# Sheet1.net
KiCad netlist of a schematic drawn in Altium Designer
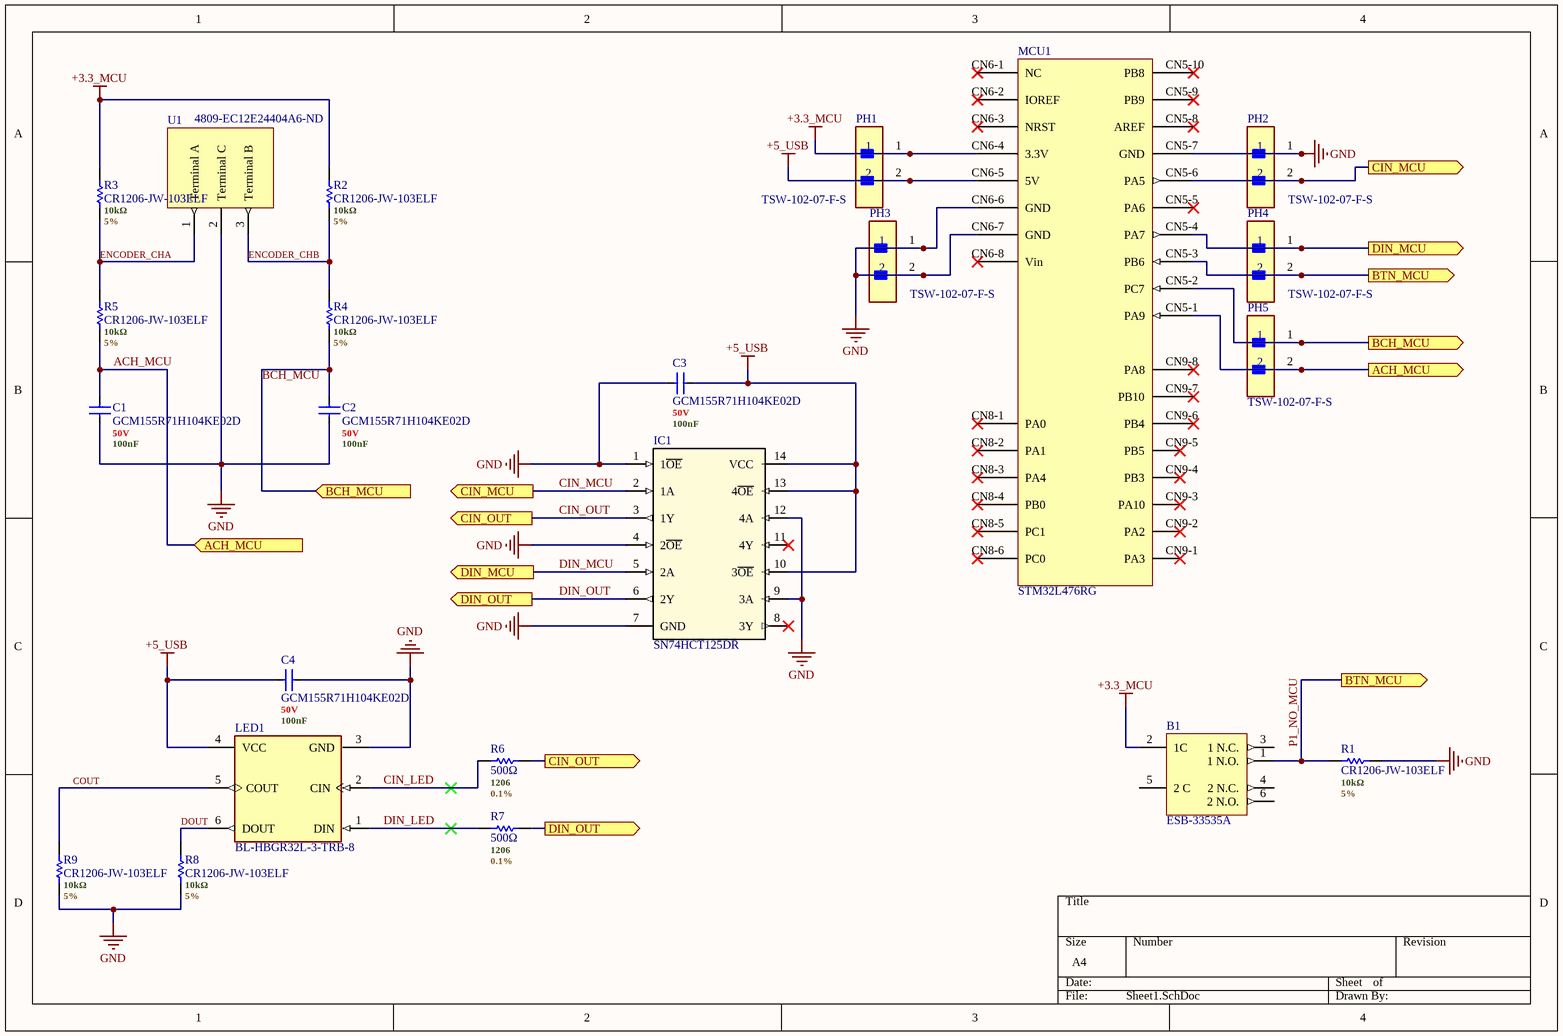
[diagram p0: Sheet1.SchDoc]

(export (version "E")
  (design (tool "Eeschema 10.0.6"))
  (components
    (comp (ref "B1")
      (value "ESB-33535A")
      (footprint "SOIC_Boton")
      (description "Pushbutton Switch, DPDT, Momentary, 0.2A, 14VDC, Solder Terminal, Surface Mount-straight")
      (fields (field (name "MANUFACTURER") "Panasonic"))
      (libsource (lib "Button") (part "ESB-33535A"))
    )
    (comp (ref "C1")
      (value "GCM155R71H104KE02D")
      (footprint "GCM155R71H104KE02D")
      (description "50V 100nF X7R ±10% 0402 Multilayer Ceramic Capacitors MLCC - SMD/SMT ROHS")
      (fields
        (field (name "MANUFACTURER") "Murata")
        (field (name "TOLERANCE") "10%")
        (field (name ".VOLTAGE RATING (DC)") "50V")
        (field (name ".VALUE") "100nF")
      )
      (libsource (lib "CAPACITOR_100nF") (part "GCM155R71H104KE02D"))
    )
    (comp (ref "C2")
      (value "GCM155R71H104KE02D")
      (footprint "GCM155R71H104KE02D")
      (description "50V 100nF X7R ±10% 0402 Multilayer Ceramic Capacitors MLCC - SMD/SMT ROHS")
      (fields
        (field (name "MANUFACTURER") "Murata")
        (field (name "TOLERANCE") "10%")
        (field (name ".VOLTAGE RATING (DC)") "50V")
        (field (name ".VALUE") "100nF")
      )
      (libsource (lib "CAPACITOR_100nF") (part "GCM155R71H104KE02D"))
    )
    (comp (ref "C3")
      (value "GCM155R71H104KE02D")
      (footprint "GCM155R71H104KE02D")
      (description "50V 100nF X7R ±10% 0402 Multilayer Ceramic Capacitors MLCC - SMD/SMT ROHS")
      (fields
        (field (name "MANUFACTURER") "Murata")
        (field (name "TOLERANCE") "10%")
        (field (name ".VOLTAGE RATING (DC)") "50V")
        (field (name ".VALUE") "100nF")
      )
      (libsource (lib "CAPACITOR_100nF") (part "GCM155R71H104KE02D"))
    )
    (comp (ref "C4")
      (value "GCM155R71H104KE02D")
      (footprint "GCM155R71H104KE02D")
      (description "50V 100nF X7R ±10% 0402 Multilayer Ceramic Capacitors MLCC - SMD/SMT ROHS")
      (fields
        (field (name "MANUFACTURER") "Murata")
        (field (name "TOLERANCE") "10%")
        (field (name ".VOLTAGE RATING (DC)") "50V")
        (field (name ".VALUE") "100nF")
      )
      (libsource (lib "CAPACITOR_100nF") (part "GCM155R71H104KE02D"))
    )
    (comp (ref "IC1")
      (value "SN74HCT125DR")
      (footprint "SOIC127P600X175_HS-15N - TI")
      (description "Buffer/Line Driver 4-CH Non-Inverting 3-ST CMOS 14-Pin SOIC T/R / IC BUS BUFF TRI-ST QD 14SOIC")
      (fields (field (name "MANUFACTURER") "Texas Instruments"))
      (libsource (lib "LVL_SHFT_SN74HCT125DR") (part "SN74HCT125DR"))
    )
    (comp (ref "LED1")
      (value "BL-HBGR32L-3-TRB-8")
      (footprint "SOIC_LEDRGB")
      (description "Address Led Discrete Serial Rgb")
      (fields (field (name "MANUFACTURER") "American Bright"))
      (libsource (lib "LED_RGB") (part "BL-HBGR32L-3-TRB-8"))
    )
    (comp (ref "MCU1")
      (value "STM32L476RG")
      (footprint "Nucleo_Card")
      (description "Development Board, STM32L476RG MCU, On-Board STLINK/V2-1, Arduino & ST Morpho Connectivity")
      (fields
        (field (name "MANUFACTURER") "STMicroelectronics")
        (field (name "MANUFACTURER PART NUMBER") "NUCLEO-L476RG")
      )
      (libsource (lib "MCU_Generico") (part "STM32L476RG"))
    )
    (comp (ref "PH1")
      (value "TSW-102-07-F-S")
      (footprint "TSW-102-07-F-S")
      (description "2 Positions Header, Unshrouded Connector 0.100\" (2.54mm) Through Hole Gold")
      (fields (field (name "MANUFACTURER") "Samtec"))
      (libsource (lib "PIN") (part "TSW-102-07-F-S"))
    )
    (comp (ref "PH2")
      (value "TSW-102-07-F-S")
      (footprint "TSW-102-07-F-S")
      (description "2 Positions Header, Unshrouded Connector 0.100\" (2.54mm) Through Hole Gold")
      (fields (field (name "MANUFACTURER") "Samtec"))
      (libsource (lib "PIN") (part "TSW-102-07-F-S"))
    )
    (comp (ref "PH3")
      (value "TSW-102-07-F-S")
      (footprint "TSW-102-07-F-S")
      (description "2 Positions Header, Unshrouded Connector 0.100\" (2.54mm) Through Hole Gold")
      (fields (field (name "MANUFACTURER") "Samtec"))
      (libsource (lib "PIN") (part "TSW-102-07-F-S"))
    )
    (comp (ref "PH4")
      (value "TSW-102-07-F-S")
      (footprint "TSW-102-07-F-S")
      (description "2 Positions Header, Unshrouded Connector 0.100\" (2.54mm) Through Hole Gold")
      (fields (field (name "MANUFACTURER") "Samtec"))
      (libsource (lib "PIN") (part "TSW-102-07-F-S"))
    )
    (comp (ref "PH5")
      (value "TSW-102-07-F-S")
      (footprint "TSW-102-07-F-S")
      (description "2 Positions Header, Unshrouded Connector 0.100\" (2.54mm) Through Hole Gold")
      (fields (field (name "MANUFACTURER") "Samtec"))
      (libsource (lib "PIN") (part "TSW-102-07-F-S"))
    )
    (comp (ref "R1")
      (value "CR1206-JW-103ELF")
      (footprint "Chip-Resistor-10k")
      (description "SMD Chip Resistor, 10 kOhm, ± 5%, 250 mW, 1206 [3216 Metric], Thick Film, General Purpose")
      (fields
        (field (name "MANUFACTURER") "Vishay")
        (field (name "MANUFACTURER PART NUMBER") "CRCW120610K0JNEA")
        (field (name ".VALUE") "10kΩ")
        (field (name ".TOLERANCE") "5%")
      )
      (libsource (lib "RESISTOR_10k") (part "CR1206-JW-103ELF"))
    )
    (comp (ref "R2")
      (value "CR1206-JW-103ELF")
      (footprint "Chip-Resistor-10k")
      (description "SMD Chip Resistor, 10 kOhm, ± 5%, 250 mW, 1206 [3216 Metric], Thick Film, General Purpose")
      (fields
        (field (name "MANUFACTURER") "Vishay")
        (field (name "MANUFACTURER PART NUMBER") "CRCW120610K0JNEA")
        (field (name ".VALUE") "10kΩ")
        (field (name ".TOLERANCE") "5%")
      )
      (libsource (lib "RESISTOR_10k") (part "CR1206-JW-103ELF"))
    )
    (comp (ref "R3")
      (value "CR1206-JW-103ELF")
      (footprint "Chip-Resistor-10k")
      (description "SMD Chip Resistor, 10 kOhm, ± 5%, 250 mW, 1206 [3216 Metric], Thick Film, General Purpose")
      (fields
        (field (name "MANUFACTURER") "Vishay")
        (field (name "MANUFACTURER PART NUMBER") "CRCW120610K0JNEA")
        (field (name ".VALUE") "10kΩ")
        (field (name ".TOLERANCE") "5%")
      )
      (libsource (lib "RESISTOR_10k") (part "CR1206-JW-103ELF"))
    )
    (comp (ref "R4")
      (value "CR1206-JW-103ELF")
      (footprint "Chip-Resistor-10k")
      (description "SMD Chip Resistor, 10 kOhm, ± 5%, 250 mW, 1206 [3216 Metric], Thick Film, General Purpose")
      (fields
        (field (name "MANUFACTURER") "Vishay")
        (field (name "MANUFACTURER PART NUMBER") "CRCW120610K0JNEA")
        (field (name ".VALUE") "10kΩ")
        (field (name ".TOLERANCE") "5%")
      )
      (libsource (lib "RESISTOR_10k") (part "CR1206-JW-103ELF"))
    )
    (comp (ref "R5")
      (value "CR1206-JW-103ELF")
      (footprint "Chip-Resistor-10k")
      (description "SMD Chip Resistor, 10 kOhm, ± 5%, 250 mW, 1206 [3216 Metric], Thick Film, General Purpose")
      (fields
        (field (name "MANUFACTURER") "Vishay")
        (field (name "MANUFACTURER PART NUMBER") "CRCW120610K0JNEA")
        (field (name ".VALUE") "10kΩ")
        (field (name ".TOLERANCE") "5%")
      )
      (libsource (lib "RESISTOR_10k") (part "CR1206-JW-103ELF"))
    )
    (comp (ref "R6")
      (value "500Ω")
      (footprint "R1206 - YAGEO")
      (description "Res Thin Film 1206 500 Ohm 0.1% 0.125W ±5ppm/°C Molded SMD Paper T/R")
      (fields
        (field (name ".CASE/PACKAGE") "1206")
        (field (name ".TOLERANCE") "0.1%")
        (field (name "MANUFACTURER") "Stackpole Electronics")
        (field (name "MANUFACTURER PART NUMBER") "RNCF1206BKY500R")
      )
      (libsource (lib "RESISTOR - GENERIC - 050325") (part "RESISTOR - GENERIC"))
    )
    (comp (ref "R7")
      (value "500Ω")
      (footprint "R1206 - YAGEO")
      (description "Res Thin Film 1206 500 Ohm 0.1% 0.125W ±5ppm/°C Molded SMD Paper T/R")
      (fields
        (field (name ".CASE/PACKAGE") "1206")
        (field (name ".TOLERANCE") "0.1%")
        (field (name "MANUFACTURER") "Stackpole Electronics")
        (field (name "MANUFACTURER PART NUMBER") "RNCF1206BKY500R")
      )
      (libsource (lib "RESISTOR - GENERIC - 050325") (part "RESISTOR - GENERIC"))
    )
    (comp (ref "R8")
      (value "CR1206-JW-103ELF")
      (footprint "Chip-Resistor-10k")
      (description "SMD Chip Resistor, 10 kOhm, ± 5%, 250 mW, 1206 [3216 Metric], Thick Film, General Purpose")
      (fields
        (field (name "MANUFACTURER") "Vishay")
        (field (name "MANUFACTURER PART NUMBER") "CRCW120610K0JNEA")
        (field (name ".VALUE") "10kΩ")
        (field (name ".TOLERANCE") "5%")
      )
      (libsource (lib "RESISTOR_10k") (part "CR1206-JW-103ELF"))
    )
    (comp (ref "R9")
      (value "CR1206-JW-103ELF")
      (footprint "Chip-Resistor-10k")
      (description "SMD Chip Resistor, 10 kOhm, ± 5%, 250 mW, 1206 [3216 Metric], Thick Film, General Purpose")
      (fields
        (field (name "MANUFACTURER") "Vishay")
        (field (name "MANUFACTURER PART NUMBER") "CRCW120610K0JNEA")
        (field (name ".VALUE") "10kΩ")
        (field (name ".TOLERANCE") "5%")
      )
      (libsource (lib "RESISTOR_10k") (part "CR1206-JW-103ELF"))
    )
    (comp (ref "U1")
      (value "4809-EC12E24404A6-ND")
      (footprint "Tray - ALPS Alpine")
      (description "Rotary Position Encoder, Single, 2 Channels")
      (fields (field (name "MANUFACTURER") "ALPS") (field (name "MANUFACTURER PART NUMBER") "EC12E24404A6"))
      (libsource (lib "Encoder_Optico") (part "4809-EC12E24404A6-ND"))
    )
  )
  (nets
    (net (code "1") (name "+3.3_MCU") (class "Default")
      (node (ref "B1") (pin "2") (pinfunction "1C_2") (pintype "passive"))
      (node (ref "MCU1") (pin "CN6-4") (pinfunction "3.3V_CN6-4") (pintype "power_in"))
      (node (ref "PH1") (pin "1") (pinfunction "1_1") (pintype "passive"))
      (node (ref "R2") (pin "2") (pinfunction "2_2") (pintype "passive"))
      (node (ref "R3") (pin "2") (pinfunction "2_2") (pintype "passive"))
    )
    (net (code "2") (name "+5_USB") (class "Default")
      (node (ref "C3") (pin "2") (pinfunction "PIN2_2") (pintype "passive"))
      (node (ref "C4") (pin "1") (pinfunction "PIN1_1") (pintype "passive"))
      (node (ref "IC1") (pin "10") (pinfunction "3~{OE}_10") (pintype "input"))
      (node (ref "IC1") (pin "13") (pinfunction "4~{OE}_13") (pintype "input"))
      (node (ref "IC1") (pin "14") (pinfunction "VCC_14") (pintype "power_in"))
      (node (ref "LED1") (pin "4") (pinfunction "VCC_4") (pintype "power_in"))
      (node (ref "MCU1") (pin "CN6-5") (pinfunction "5V_CN6-5") (pintype "power_in"))
      (node (ref "PH1") (pin "2") (pinfunction "2_2") (pintype "passive"))
    )
    (net (code "3") (name "/ACH_MCU") (class "Default")
      (node (ref "C1") (pin "2") (pinfunction "PIN2_2") (pintype "passive"))
      (node (ref "MCU1") (pin "CN5-1") (pinfunction "PA9_CN5-1") (pintype "input"))
      (node (ref "PH5") (pin "2") (pinfunction "2_2") (pintype "passive"))
      (node (ref "R5") (pin "1") (pinfunction "1_1") (pintype "passive"))
    )
    (net (code "4") (name "/BCH_MCU") (class "Default")
      (node (ref "C2") (pin "2") (pinfunction "PIN2_2") (pintype "passive"))
      (node (ref "MCU1") (pin "CN5-2") (pinfunction "PC7_CN5-2") (pintype "input"))
      (node (ref "PH5") (pin "1") (pinfunction "1_1") (pintype "passive"))
      (node (ref "R4") (pin "1") (pinfunction "1_1") (pintype "passive"))
    )
    (net (code "5") (name "/CIN_LED") (class "Default")
      (node (ref "LED1") (pin "2") (pinfunction "CIN_2") (pintype "input"))
      (node (ref "R6") (pin "1") (pinfunction "1_1") (pintype "passive"))
    )
    (net (code "6") (name "/CIN_MCU") (class "Default")
      (node (ref "IC1") (pin "2") (pinfunction "1A_2") (pintype "input"))
      (node (ref "MCU1") (pin "CN5-6") (pinfunction "PA5_CN5-6") (pintype "output"))
      (node (ref "PH2") (pin "2") (pinfunction "2_2") (pintype "passive"))
    )
    (net (code "7") (name "/CIN_OUT") (class "Default")
      (node (ref "IC1") (pin "3") (pinfunction "1Y_3") (pintype "output"))
      (node (ref "R6") (pin "2") (pinfunction "2_2") (pintype "passive"))
    )
    (net (code "8") (name "/COUT") (class "Default")
      (node (ref "LED1") (pin "5") (pinfunction "COUT_5") (pintype "output"))
      (node (ref "R9") (pin "2") (pinfunction "2_2") (pintype "passive"))
    )
    (net (code "9") (name "/DIN_LED") (class "Default")
      (node (ref "LED1") (pin "1") (pinfunction "DIN_1") (pintype "input"))
      (node (ref "R7") (pin "1") (pinfunction "1_1") (pintype "passive"))
    )
    (net (code "10") (name "/DIN_MCU") (class "Default")
      (node (ref "IC1") (pin "5") (pinfunction "2A_5") (pintype "input"))
      (node (ref "MCU1") (pin "CN5-4") (pinfunction "PA7_CN5-4") (pintype "output"))
      (node (ref "PH4") (pin "1") (pinfunction "1_1") (pintype "passive"))
    )
    (net (code "11") (name "/DIN_OUT") (class "Default")
      (node (ref "IC1") (pin "6") (pinfunction "2Y_6") (pintype "output"))
      (node (ref "R7") (pin "2") (pinfunction "2_2") (pintype "passive"))
    )
    (net (code "12") (name "/DOUT") (class "Default")
      (node (ref "LED1") (pin "6") (pinfunction "DOUT_6") (pintype "output"))
      (node (ref "R8") (pin "2") (pinfunction "2_2") (pintype "passive"))
    )
    (net (code "13") (name "/ENCODER_CHA") (class "Default")
      (node (ref "R3") (pin "1") (pinfunction "1_1") (pintype "passive"))
      (node (ref "R5") (pin "2") (pinfunction "2_2") (pintype "passive"))
      (node (ref "U1") (pin "1") (pinfunction "Terminal_A_1") (pintype "output"))
    )
    (net (code "14") (name "/ENCODER_CHB") (class "Default")
      (node (ref "R2") (pin "1") (pinfunction "1_1") (pintype "passive"))
      (node (ref "R4") (pin "2") (pinfunction "2_2") (pintype "passive"))
      (node (ref "U1") (pin "3") (pinfunction "Terminal_B_3") (pintype "output"))
    )
    (net (code "15") (name "/P1_NO_MCU") (class "Default")
      (node (ref "B1") (pin "1") (pinfunction "1_N.O._1") (pintype "output"))
      (node (ref "MCU1") (pin "CN5-3") (pinfunction "PB6_CN5-3") (pintype "input"))
      (node (ref "PH4") (pin "2") (pinfunction "2_2") (pintype "passive"))
      (node (ref "R1") (pin "1") (pinfunction "1_1") (pintype "passive"))
    )
    (net (code "16") (name "GND") (class "Default")
      (node (ref "C1") (pin "1") (pinfunction "PIN1_1") (pintype "passive"))
      (node (ref "C2") (pin "1") (pinfunction "PIN1_1") (pintype "passive"))
      (node (ref "C3") (pin "1") (pinfunction "PIN1_1") (pintype "passive"))
      (node (ref "C4") (pin "2") (pinfunction "PIN2_2") (pintype "passive"))
      (node (ref "IC1") (pin "1") (pinfunction "1~{OE}_1") (pintype "input"))
      (node (ref "IC1") (pin "12") (pinfunction "4A_12") (pintype "input"))
      (node (ref "IC1") (pin "4") (pinfunction "2~{OE}_4") (pintype "input"))
      (node (ref "IC1") (pin "7") (pinfunction "GND_7") (pintype "power_in"))
      (node (ref "IC1") (pin "9") (pinfunction "3A_9") (pintype "input"))
      (node (ref "LED1") (pin "3") (pinfunction "GND_3") (pintype "power_in"))
      (node (ref "MCU1") (pin "CN5-7") (pinfunction "GND_CN5-7") (pintype "power_in"))
      (node (ref "MCU1") (pin "CN6-6") (pinfunction "GND_CN6-6") (pintype "power_in"))
      (node (ref "MCU1") (pin "CN6-7") (pinfunction "GND_CN6-7") (pintype "power_in"))
      (node (ref "PH2") (pin "1") (pinfunction "1_1") (pintype "passive"))
      (node (ref "PH3") (pin "1") (pinfunction "1_1") (pintype "passive"))
      (node (ref "PH3") (pin "2") (pinfunction "2_2") (pintype "passive"))
      (node (ref "R1") (pin "2") (pinfunction "2_2") (pintype "passive"))
      (node (ref "R8") (pin "1") (pinfunction "1_1") (pintype "passive"))
      (node (ref "R9") (pin "1") (pinfunction "1_1") (pintype "passive"))
      (node (ref "U1") (pin "2") (pinfunction "Terminal_C_2") (pintype "power_in"))
    )
    (net (code "17") (name "unconnected-(B1-1_N.C.-Pad3)") (class "Default")
      (node (ref "B1") (pin "3") (pinfunction "1_N.C._3") (pintype "output"))
    )
    (net (code "18") (name "unconnected-(B1-2_C-Pad5)") (class "Default")
      (node (ref "B1") (pin "5") (pinfunction "2_C_5") (pintype "passive"))
    )
    (net (code "19") (name "unconnected-(B1-2_N.C.-Pad4)") (class "Default")
      (node (ref "B1") (pin "4") (pinfunction "2_N.C._4") (pintype "output"))
    )
    (net (code "20") (name "unconnected-(B1-2_N.O.-Pad6)") (class "Default")
      (node (ref "B1") (pin "6") (pinfunction "2_N.O._6") (pintype "output"))
    )
    (net (code "21") (name "unconnected-(IC1-3Y-Pad8)") (class "Default")
      (node (ref "IC1") (pin "8") (pinfunction "3Y_8") (pintype "output+no_connect"))
    )
    (net (code "22") (name "unconnected-(IC1-4Y-Pad11)") (class "Default")
      (node (ref "IC1") (pin "11") (pinfunction "4Y_11") (pintype "input+no_connect"))
    )
    (net (code "23") (name "unconnected-(MCU1-AREF-PadCN5-8)") (class "Default")
      (node (ref "MCU1") (pin "CN5-8") (pinfunction "AREF_CN5-8") (pintype "passive+no_connect"))
    )
    (net (code "24") (name "unconnected-(MCU1-IOREF-PadCN6-2)") (class "Default")
      (node (ref "MCU1") (pin "CN6-2") (pinfunction "IOREF_CN6-2") (pintype "passive+no_connect"))
    )
    (net (code "25") (name "unconnected-(MCU1-NC-PadCN6-1)") (class "Default")
      (node (ref "MCU1") (pin "CN6-1") (pinfunction "NC_CN6-1") (pintype "passive+no_connect"))
    )
    (net (code "26") (name "unconnected-(MCU1-NRST-PadCN6-3)") (class "Default")
      (node (ref "MCU1") (pin "CN6-3") (pinfunction "NRST_CN6-3") (pintype "passive+no_connect"))
    )
    (net (code "27") (name "unconnected-(MCU1-PA0-PadCN8-1)") (class "Default")
      (node (ref "MCU1") (pin "CN8-1") (pinfunction "PA0_CN8-1") (pintype "passive+no_connect"))
    )
    (net (code "28") (name "unconnected-(MCU1-PA1-PadCN8-2)") (class "Default")
      (node (ref "MCU1") (pin "CN8-2") (pinfunction "PA1_CN8-2") (pintype "passive+no_connect"))
    )
    (net (code "29") (name "unconnected-(MCU1-PA2-PadCN9-2)") (class "Default")
      (node (ref "MCU1") (pin "CN9-2") (pinfunction "PA2_CN9-2") (pintype "passive+no_connect"))
    )
    (net (code "30") (name "unconnected-(MCU1-PA3-PadCN9-1)") (class "Default")
      (node (ref "MCU1") (pin "CN9-1") (pinfunction "PA3_CN9-1") (pintype "passive+no_connect"))
    )
    (net (code "31") (name "unconnected-(MCU1-PA4-PadCN8-3)") (class "Default")
      (node (ref "MCU1") (pin "CN8-3") (pinfunction "PA4_CN8-3") (pintype "passive+no_connect"))
    )
    (net (code "32") (name "unconnected-(MCU1-PA6-PadCN5-5)") (class "Default")
      (node (ref "MCU1") (pin "CN5-5") (pinfunction "PA6_CN5-5") (pintype "passive+no_connect"))
    )
    (net (code "33") (name "unconnected-(MCU1-PA8-PadCN9-8)") (class "Default")
      (node (ref "MCU1") (pin "CN9-8") (pinfunction "PA8_CN9-8") (pintype "passive+no_connect"))
    )
    (net (code "34") (name "unconnected-(MCU1-PA10-PadCN9-3)") (class "Default")
      (node (ref "MCU1") (pin "CN9-3") (pinfunction "PA10_CN9-3") (pintype "passive+no_connect"))
    )
    (net (code "35") (name "unconnected-(MCU1-PB0-PadCN8-4)") (class "Default")
      (node (ref "MCU1") (pin "CN8-4") (pinfunction "PB0_CN8-4") (pintype "passive+no_connect"))
    )
    (net (code "36") (name "unconnected-(MCU1-PB3-PadCN9-4)") (class "Default")
      (node (ref "MCU1") (pin "CN9-4") (pinfunction "PB3_CN9-4") (pintype "passive+no_connect"))
    )
    (net (code "37") (name "unconnected-(MCU1-PB4-PadCN9-6)") (class "Default")
      (node (ref "MCU1") (pin "CN9-6") (pinfunction "PB4_CN9-6") (pintype "passive+no_connect"))
    )
    (net (code "38") (name "unconnected-(MCU1-PB5-PadCN9-5)") (class "Default")
      (node (ref "MCU1") (pin "CN9-5") (pinfunction "PB5_CN9-5") (pintype "passive+no_connect"))
    )
    (net (code "39") (name "unconnected-(MCU1-PB8-PadCN5-10)") (class "Default")
      (node (ref "MCU1") (pin "CN5-10") (pinfunction "PB8_CN5-10") (pintype "passive+no_connect"))
    )
    (net (code "40") (name "unconnected-(MCU1-PB9-PadCN5-9)") (class "Default")
      (node (ref "MCU1") (pin "CN5-9") (pinfunction "PB9_CN5-9") (pintype "passive+no_connect"))
    )
    (net (code "41") (name "unconnected-(MCU1-PB10-PadCN9-7)") (class "Default")
      (node (ref "MCU1") (pin "CN9-7") (pinfunction "PB10_CN9-7") (pintype "passive+no_connect"))
    )
    (net (code "42") (name "unconnected-(MCU1-PC0-PadCN8-6)") (class "Default")
      (node (ref "MCU1") (pin "CN8-6") (pinfunction "PC0_CN8-6") (pintype "passive+no_connect"))
    )
    (net (code "43") (name "unconnected-(MCU1-PC1-PadCN8-5)") (class "Default")
      (node (ref "MCU1") (pin "CN8-5") (pinfunction "PC1_CN8-5") (pintype "passive+no_connect"))
    )
    (net (code "44") (name "unconnected-(MCU1-Vin-PadCN6-8)") (class "Default")
      (node (ref "MCU1") (pin "CN6-8") (pinfunction "Vin_CN6-8") (pintype "passive+no_connect"))
    )
  )
)
